# BBB_Breakout_Cape.net
KiCad netlist of a schematic drawn in EAGLE
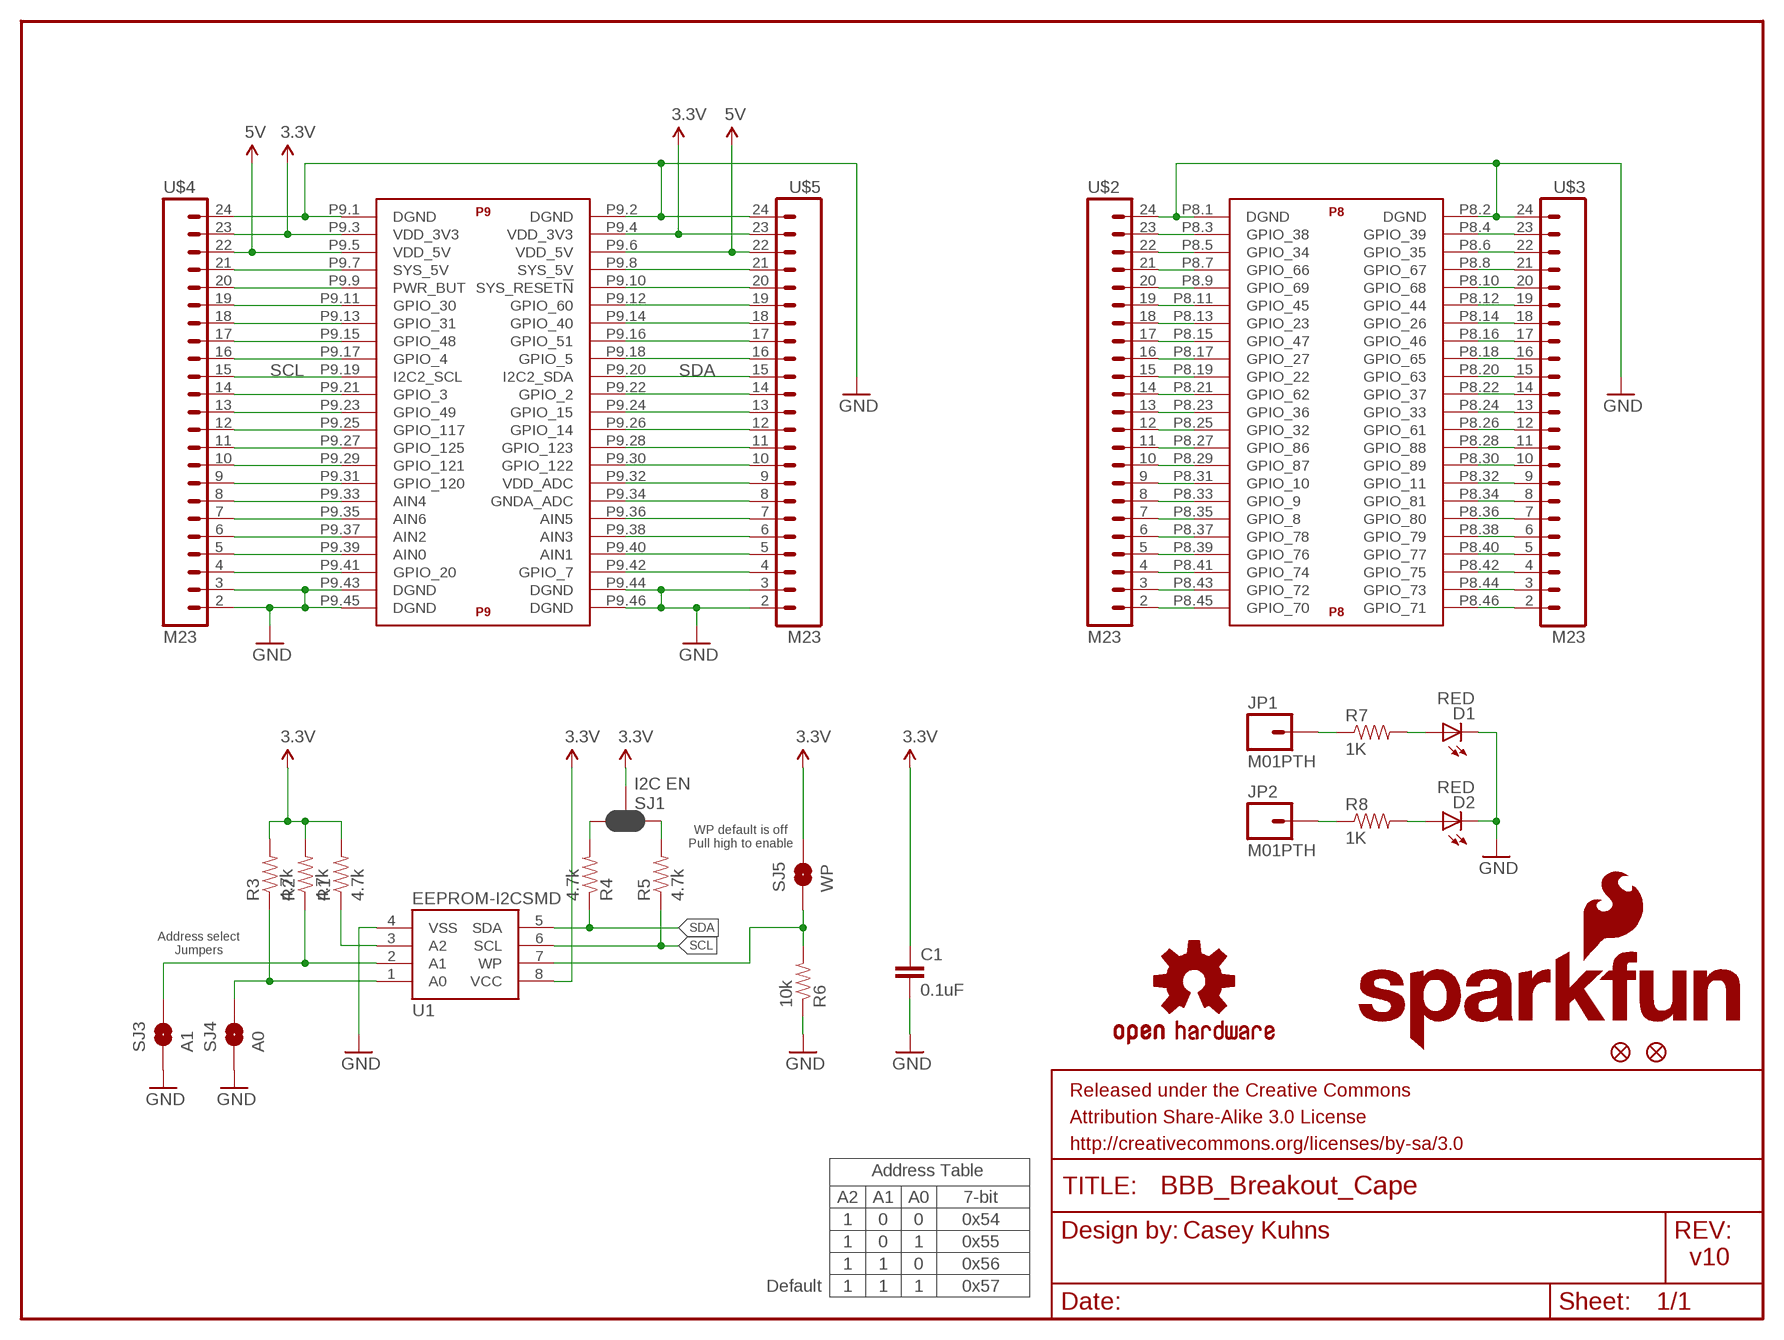
[diagram p0: schematic, sheet 1]

(export (version "E")
  (design (tool "Eeschema 10.0.6"))
  (components
    (comp (ref "C1")
      (value "0.1uF")
      (footprint "eagle-import:0603-CAP")
      (libsource (lib "eagle-import") (part "0.1UF-25V(+80/-20%)(0603)"))
    )
    (comp (ref "D1")
      (value "RED")
      (footprint "eagle-import:LED-0603")
      (libsource (lib "eagle-import") (part "LED-RED0603"))
    )
    (comp (ref "D2")
      (value "RED")
      (footprint "eagle-import:LED-0603")
      (libsource (lib "eagle-import") (part "LED-RED0603"))
    )
    (comp (ref "FID1")
      (value "FIDUCIAL1X2")
      (footprint "eagle-import:FIDUCIAL-1X2")
      (libsource (lib "eagle-import") (part "FIDUCIAL1X2"))
    )
    (comp (ref "FID2")
      (value "FIDUCIAL1X2")
      (footprint "eagle-import:FIDUCIAL-1X2")
      (libsource (lib "eagle-import") (part "FIDUCIAL1X2"))
    )
    (comp (ref "FRAME1")
      (value "FRAME-LETTER")
      (footprint "eagle-import:CREATIVE_COMMONS")
      (libsource (lib "eagle-import") (part "FRAME-LETTER"))
    )
    (comp (ref "JP1")
      (value "M01PTH")
      (footprint "eagle-import:1X01")
      (libsource (lib "eagle-import") (part "M01PTH"))
    )
    (comp (ref "JP2")
      (value "M01PTH")
      (footprint "eagle-import:1X01")
      (libsource (lib "eagle-import") (part "M01PTH"))
    )
    (comp (ref "LOGO2")
      (value "OSHW-LOGOS")
      (footprint "eagle-import:OSHW-LOGO-S")
      (libsource (lib "eagle-import") (part "OSHW-LOGOS"))
    )
    (comp (ref "LOGO3")
      (value "SFE_LOGO_NAME_FLAME.1_INCH")
      (footprint "eagle-import:SFE_LOGO_NAME_FLAME_.1")
      (libsource (lib "eagle-import") (part "SFE_LOGO_NAME_FLAME.1_INCH"))
    )
    (comp (ref "R1")
      (value "4.7k")
      (footprint "eagle-import:0603@1")
      (libsource (lib "eagle-import") (part "4.7KOHM1/10W1%(0603)"))
    )
    (comp (ref "R2")
      (value "4.7k")
      (footprint "eagle-import:0603@1")
      (libsource (lib "eagle-import") (part "4.7KOHM1/10W1%(0603)"))
    )
    (comp (ref "R3")
      (value "4.7k")
      (footprint "eagle-import:0603@1")
      (libsource (lib "eagle-import") (part "4.7KOHM1/10W1%(0603)"))
    )
    (comp (ref "R4")
      (value "4.7k")
      (footprint "eagle-import:0603@1")
      (fields (field (name "PROD_ID") "RES-07857"))
      (libsource (lib "eagle-import") (part "4.7KOHM1/10W1%(0603)"))
    )
    (comp (ref "R5")
      (value "4.7k")
      (footprint "eagle-import:0603@1")
      (fields (field (name "PROD_ID") "RES-07857"))
      (libsource (lib "eagle-import") (part "4.7KOHM1/10W1%(0603)"))
    )
    (comp (ref "R6")
      (value "10k")
      (footprint "eagle-import:0603-RES")
      (libsource (lib "eagle-import") (part "10KOHM1/10W1%(0603)0603"))
    )
    (comp (ref "R7")
      (value "1K")
      (footprint "eagle-import:0603-RES")
      (libsource (lib "eagle-import") (part "1KOHM1/10W1%(0603)"))
    )
    (comp (ref "R8")
      (value "1K")
      (footprint "eagle-import:0603-RES")
      (libsource (lib "eagle-import") (part "1KOHM1/10W1%(0603)"))
    )
    (comp (ref "SJ1")
      (value "I2C EN")
      (footprint "eagle-import:SMT-JUMPER_3_2-NC_PASTE_SILK")
      (libsource (lib "eagle-import") (part "JUMPER-SMT_3_2-NC_PASTE_SILK"))
    )
    (comp (ref "SJ3")
      (value "A1")
      (footprint "eagle-import:SMT-JUMPER_2_NO_SILK")
      (libsource (lib "eagle-import") (part "JUMPER-SMT_2_NO_SILK"))
    )
    (comp (ref "SJ4")
      (value "A0")
      (footprint "eagle-import:SMT-JUMPER_2_NO_SILK")
      (libsource (lib "eagle-import") (part "JUMPER-SMT_2_NO_SILK"))
    )
    (comp (ref "SJ5")
      (value "WP")
      (footprint "eagle-import:SMT-JUMPER_2_NO_SILK")
      (libsource (lib "eagle-import") (part "JUMPER-SMT_2_NO_SILK"))
    )
    (comp (ref "U$1")
      (value "BEAGLE_BONE_BLACK_CAPE")
      (footprint "eagle-import:BEAGLE_BONE_BLACK_CAPE")
      (libsource (lib "eagle-import") (part "BEAGLE_BONE_BLACK_CAPE"))
    )
    (comp (ref "U$2")
      (value "M23")
      (footprint "eagle-import:1X23")
      (libsource (lib "eagle-import") (part "M23"))
    )
    (comp (ref "U$3")
      (value "M23")
      (footprint "eagle-import:1X23")
      (libsource (lib "eagle-import") (part "M23"))
    )
    (comp (ref "U$4")
      (value "M23")
      (footprint "eagle-import:1X23")
      (libsource (lib "eagle-import") (part "M23"))
    )
    (comp (ref "U$5")
      (value "M23")
      (footprint "eagle-import:1X23")
      (libsource (lib "eagle-import") (part "M23"))
    )
    (comp (ref "U1")
      (value "EEPROM-I2CSMD")
      (footprint "eagle-import:SO08")
      (libsource (lib "eagle-import") (part "EEPROM-I2CSMD"))
    )
  )
  (nets
    (net (code "1") (name "3.3V") (class "Default")
      (node (ref "C1") (pin "1") (pinfunction "1_1") (pintype "passive"))
      (node (ref "R1") (pin "2") (pinfunction "2_2") (pintype "passive"))
      (node (ref "R2") (pin "2") (pinfunction "2_2") (pintype "passive"))
      (node (ref "R3") (pin "2") (pinfunction "2_2") (pintype "passive"))
      (node (ref "SJ1") (pin "2") (pinfunction "2_2") (pintype "passive"))
      (node (ref "SJ5") (pin "2") (pinfunction "2_2") (pintype "passive"))
      (node (ref "U$1") (pin "P9.3") (pinfunction "VDD_3V3_P9.3") (pintype "bidirectional"))
      (node (ref "U$1") (pin "P9.4") (pinfunction "VDD_3V3_P9.4") (pintype "bidirectional"))
      (node (ref "U$4") (pin "23") (pinfunction "23_23") (pintype "passive"))
      (node (ref "U$5") (pin "23") (pinfunction "23_23") (pintype "passive"))
      (node (ref "U1") (pin "8") (pinfunction "VCC_8") (pintype "power_in"))
    )
    (net (code "2") (name "5V") (class "Default")
      (node (ref "U$1") (pin "P9.5") (pinfunction "VDD_5V_P9.5") (pintype "bidirectional"))
      (node (ref "U$1") (pin "P9.6") (pinfunction "VDD_5V_P9.6") (pintype "bidirectional"))
      (node (ref "U$4") (pin "22") (pinfunction "22_22") (pintype "passive"))
      (node (ref "U$5") (pin "22") (pinfunction "22_22") (pintype "passive"))
    )
    (net (code "3") (name "GND") (class "Default")
      (node (ref "C1") (pin "2") (pinfunction "2_2") (pintype "passive"))
      (node (ref "D1") (pin "C") (pinfunction "C_C") (pintype "passive"))
      (node (ref "D2") (pin "C") (pinfunction "C_C") (pintype "passive"))
      (node (ref "R6") (pin "1") (pinfunction "1_1") (pintype "passive"))
      (node (ref "SJ3") (pin "1") (pinfunction "1_1") (pintype "passive"))
      (node (ref "SJ4") (pin "1") (pinfunction "1_1") (pintype "passive"))
      (node (ref "U$1") (pin "P8.1") (pinfunction "DGND_P8.1") (pintype "bidirectional"))
      (node (ref "U$1") (pin "P8.2") (pinfunction "DGND_P8.2") (pintype "bidirectional"))
      (node (ref "U$1") (pin "P9.1") (pinfunction "DGND_P9.1") (pintype "bidirectional"))
      (node (ref "U$1") (pin "P9.2") (pinfunction "DGND_P9.2") (pintype "bidirectional"))
      (node (ref "U$1") (pin "P9.43") (pinfunction "DGND_P9.43") (pintype "bidirectional"))
      (node (ref "U$1") (pin "P9.44") (pinfunction "DGND_P9.44") (pintype "bidirectional"))
      (node (ref "U$1") (pin "P9.45") (pinfunction "DGND_P9.45") (pintype "bidirectional"))
      (node (ref "U$1") (pin "P9.46") (pinfunction "DGND_P9.46") (pintype "bidirectional"))
      (node (ref "U$2") (pin "24") (pinfunction "24_24") (pintype "passive"))
      (node (ref "U$3") (pin "24") (pinfunction "24_24") (pintype "passive"))
      (node (ref "U$4") (pin "2") (pinfunction "2_2") (pintype "passive"))
      (node (ref "U$4") (pin "24") (pinfunction "24_24") (pintype "passive"))
      (node (ref "U$4") (pin "3") (pinfunction "3_3") (pintype "passive"))
      (node (ref "U$5") (pin "2") (pinfunction "2_2") (pintype "passive"))
      (node (ref "U$5") (pin "24") (pinfunction "24_24") (pintype "passive"))
      (node (ref "U$5") (pin "3") (pinfunction "3_3") (pintype "passive"))
      (node (ref "U1") (pin "4") (pinfunction "VSS_4") (pintype "power_in"))
    )
    (net (code "4") (name "Net-(D1-PadA)") (class "Default")
      (node (ref "D1") (pin "A") (pinfunction "A_A") (pintype "passive"))
      (node (ref "R7") (pin "2") (pinfunction "2_2") (pintype "passive"))
    )
    (net (code "5") (name "Net-(D2-PadA)") (class "Default")
      (node (ref "D2") (pin "A") (pinfunction "A_A") (pintype "passive"))
      (node (ref "R8") (pin "2") (pinfunction "2_2") (pintype "passive"))
    )
    (net (code "6") (name "Net-(JP1-Pad1)") (class "Default")
      (node (ref "JP1") (pin "1") (pinfunction "1_1") (pintype "passive"))
      (node (ref "R7") (pin "1") (pinfunction "1_1") (pintype "passive"))
    )
    (net (code "7") (name "Net-(JP2-Pad1)") (class "Default")
      (node (ref "JP2") (pin "1") (pinfunction "1_1") (pintype "passive"))
      (node (ref "R8") (pin "1") (pinfunction "1_1") (pintype "passive"))
    )
    (net (code "8") (name "Net-(R4-Pad2)") (class "Default")
      (node (ref "R4") (pin "2") (pinfunction "2_2") (pintype "passive"))
      (node (ref "SJ1") (pin "3") (pinfunction "3_3") (pintype "passive"))
    )
    (net (code "9") (name "Net-(R5-Pad2)") (class "Default")
      (node (ref "R5") (pin "2") (pinfunction "2_2") (pintype "passive"))
      (node (ref "SJ1") (pin "1") (pinfunction "1_1") (pintype "passive"))
    )
    (net (code "10") (name "Net-(U$1A-GPIO_8)") (class "Default")
      (node (ref "U$1") (pin "P8.35") (pinfunction "GPIO_8_P8.35") (pintype "bidirectional"))
      (node (ref "U$2") (pin "7") (pinfunction "7_7") (pintype "passive"))
    )
    (net (code "11") (name "Net-(U$1A-GPIO_9)") (class "Default")
      (node (ref "U$1") (pin "P8.33") (pinfunction "GPIO_9_P8.33") (pintype "bidirectional"))
      (node (ref "U$2") (pin "8") (pinfunction "8_8") (pintype "passive"))
    )
    (net (code "12") (name "Net-(U$1A-GPIO_10)") (class "Default")
      (node (ref "U$1") (pin "P8.31") (pinfunction "GPIO_10_P8.31") (pintype "bidirectional"))
      (node (ref "U$2") (pin "9") (pinfunction "9_9") (pintype "passive"))
    )
    (net (code "13") (name "Net-(U$1A-GPIO_11)") (class "Default")
      (node (ref "U$1") (pin "P8.32") (pinfunction "GPIO_11_P8.32") (pintype "bidirectional"))
      (node (ref "U$3") (pin "9") (pinfunction "9_9") (pintype "passive"))
    )
    (net (code "14") (name "Net-(U$1A-GPIO_22)") (class "Default")
      (node (ref "U$1") (pin "P8.19") (pinfunction "GPIO_22_P8.19") (pintype "bidirectional"))
      (node (ref "U$2") (pin "15") (pinfunction "15_15") (pintype "passive"))
    )
    (net (code "15") (name "Net-(U$1A-GPIO_23)") (class "Default")
      (node (ref "U$1") (pin "P8.13") (pinfunction "GPIO_23_P8.13") (pintype "bidirectional"))
      (node (ref "U$2") (pin "18") (pinfunction "18_18") (pintype "passive"))
    )
    (net (code "16") (name "Net-(U$1A-GPIO_26)") (class "Default")
      (node (ref "U$1") (pin "P8.14") (pinfunction "GPIO_26_P8.14") (pintype "bidirectional"))
      (node (ref "U$3") (pin "18") (pinfunction "18_18") (pintype "passive"))
    )
    (net (code "17") (name "Net-(U$1A-GPIO_27)") (class "Default")
      (node (ref "U$1") (pin "P8.17") (pinfunction "GPIO_27_P8.17") (pintype "bidirectional"))
      (node (ref "U$2") (pin "16") (pinfunction "16_16") (pintype "passive"))
    )
    (net (code "18") (name "Net-(U$1A-GPIO_32)") (class "Default")
      (node (ref "U$1") (pin "P8.25") (pinfunction "GPIO_32_P8.25") (pintype "bidirectional"))
      (node (ref "U$2") (pin "12") (pinfunction "12_12") (pintype "passive"))
    )
    (net (code "19") (name "Net-(U$1A-GPIO_33)") (class "Default")
      (node (ref "U$1") (pin "P8.24") (pinfunction "GPIO_33_P8.24") (pintype "bidirectional"))
      (node (ref "U$3") (pin "13") (pinfunction "13_13") (pintype "passive"))
    )
    (net (code "20") (name "Net-(U$1A-GPIO_34)") (class "Default")
      (node (ref "U$1") (pin "P8.5") (pinfunction "GPIO_34_P8.5") (pintype "bidirectional"))
      (node (ref "U$2") (pin "22") (pinfunction "22_22") (pintype "passive"))
    )
    (net (code "21") (name "Net-(U$1A-GPIO_35)") (class "Default")
      (node (ref "U$1") (pin "P8.6") (pinfunction "GPIO_35_P8.6") (pintype "bidirectional"))
      (node (ref "U$3") (pin "22") (pinfunction "22_22") (pintype "passive"))
    )
    (net (code "22") (name "Net-(U$1A-GPIO_36)") (class "Default")
      (node (ref "U$1") (pin "P8.23") (pinfunction "GPIO_36_P8.23") (pintype "bidirectional"))
      (node (ref "U$2") (pin "13") (pinfunction "13_13") (pintype "passive"))
    )
    (net (code "23") (name "Net-(U$1A-GPIO_37)") (class "Default")
      (node (ref "U$1") (pin "P8.22") (pinfunction "GPIO_37_P8.22") (pintype "bidirectional"))
      (node (ref "U$3") (pin "14") (pinfunction "14_14") (pintype "passive"))
    )
    (net (code "24") (name "Net-(U$1A-GPIO_38)") (class "Default")
      (node (ref "U$1") (pin "P8.3") (pinfunction "GPIO_38_P8.3") (pintype "bidirectional"))
      (node (ref "U$2") (pin "23") (pinfunction "23_23") (pintype "passive"))
    )
    (net (code "25") (name "Net-(U$1A-GPIO_39)") (class "Default")
      (node (ref "U$1") (pin "P8.4") (pinfunction "GPIO_39_P8.4") (pintype "bidirectional"))
      (node (ref "U$3") (pin "23") (pinfunction "23_23") (pintype "passive"))
    )
    (net (code "26") (name "Net-(U$1A-GPIO_44)") (class "Default")
      (node (ref "U$1") (pin "P8.12") (pinfunction "GPIO_44_P8.12") (pintype "bidirectional"))
      (node (ref "U$3") (pin "19") (pinfunction "19_19") (pintype "passive"))
    )
    (net (code "27") (name "Net-(U$1A-GPIO_45)") (class "Default")
      (node (ref "U$1") (pin "P8.11") (pinfunction "GPIO_45_P8.11") (pintype "bidirectional"))
      (node (ref "U$2") (pin "19") (pinfunction "19_19") (pintype "passive"))
    )
    (net (code "28") (name "Net-(U$1A-GPIO_46)") (class "Default")
      (node (ref "U$1") (pin "P8.16") (pinfunction "GPIO_46_P8.16") (pintype "bidirectional"))
      (node (ref "U$3") (pin "17") (pinfunction "17_17") (pintype "passive"))
    )
    (net (code "29") (name "Net-(U$1A-GPIO_47)") (class "Default")
      (node (ref "U$1") (pin "P8.15") (pinfunction "GPIO_47_P8.15") (pintype "bidirectional"))
      (node (ref "U$2") (pin "17") (pinfunction "17_17") (pintype "passive"))
    )
    (net (code "30") (name "Net-(U$1A-GPIO_61)") (class "Default")
      (node (ref "U$1") (pin "P8.26") (pinfunction "GPIO_61_P8.26") (pintype "bidirectional"))
      (node (ref "U$3") (pin "12") (pinfunction "12_12") (pintype "passive"))
    )
    (net (code "31") (name "Net-(U$1A-GPIO_62)") (class "Default")
      (node (ref "U$1") (pin "P8.21") (pinfunction "GPIO_62_P8.21") (pintype "bidirectional"))
      (node (ref "U$2") (pin "14") (pinfunction "14_14") (pintype "passive"))
    )
    (net (code "32") (name "Net-(U$1A-GPIO_63)") (class "Default")
      (node (ref "U$1") (pin "P8.20") (pinfunction "GPIO_63_P8.20") (pintype "bidirectional"))
      (node (ref "U$3") (pin "15") (pinfunction "15_15") (pintype "passive"))
    )
    (net (code "33") (name "Net-(U$1A-GPIO_65)") (class "Default")
      (node (ref "U$1") (pin "P8.18") (pinfunction "GPIO_65_P8.18") (pintype "bidirectional"))
      (node (ref "U$3") (pin "16") (pinfunction "16_16") (pintype "passive"))
    )
    (net (code "34") (name "Net-(U$1A-GPIO_66)") (class "Default")
      (node (ref "U$1") (pin "P8.7") (pinfunction "GPIO_66_P8.7") (pintype "bidirectional"))
      (node (ref "U$2") (pin "21") (pinfunction "21_21") (pintype "passive"))
    )
    (net (code "35") (name "Net-(U$1A-GPIO_67)") (class "Default")
      (node (ref "U$1") (pin "P8.8") (pinfunction "GPIO_67_P8.8") (pintype "bidirectional"))
      (node (ref "U$3") (pin "21") (pinfunction "21_21") (pintype "passive"))
    )
    (net (code "36") (name "Net-(U$1A-GPIO_68)") (class "Default")
      (node (ref "U$1") (pin "P8.10") (pinfunction "GPIO_68_P8.10") (pintype "bidirectional"))
      (node (ref "U$3") (pin "20") (pinfunction "20_20") (pintype "passive"))
    )
    (net (code "37") (name "Net-(U$1A-GPIO_69)") (class "Default")
      (node (ref "U$1") (pin "P8.9") (pinfunction "GPIO_69_P8.9") (pintype "bidirectional"))
      (node (ref "U$2") (pin "20") (pinfunction "20_20") (pintype "passive"))
    )
    (net (code "38") (name "Net-(U$1A-GPIO_70)") (class "Default")
      (node (ref "U$1") (pin "P8.45") (pinfunction "GPIO_70_P8.45") (pintype "bidirectional"))
      (node (ref "U$2") (pin "2") (pinfunction "2_2") (pintype "passive"))
    )
    (net (code "39") (name "Net-(U$1A-GPIO_71)") (class "Default")
      (node (ref "U$1") (pin "P8.46") (pinfunction "GPIO_71_P8.46") (pintype "bidirectional"))
      (node (ref "U$3") (pin "2") (pinfunction "2_2") (pintype "passive"))
    )
    (net (code "40") (name "Net-(U$1A-GPIO_72)") (class "Default")
      (node (ref "U$1") (pin "P8.43") (pinfunction "GPIO_72_P8.43") (pintype "bidirectional"))
      (node (ref "U$2") (pin "3") (pinfunction "3_3") (pintype "passive"))
    )
    (net (code "41") (name "Net-(U$1A-GPIO_73)") (class "Default")
      (node (ref "U$1") (pin "P8.44") (pinfunction "GPIO_73_P8.44") (pintype "bidirectional"))
      (node (ref "U$3") (pin "3") (pinfunction "3_3") (pintype "passive"))
    )
    (net (code "42") (name "Net-(U$1A-GPIO_74)") (class "Default")
      (node (ref "U$1") (pin "P8.41") (pinfunction "GPIO_74_P8.41") (pintype "bidirectional"))
      (node (ref "U$2") (pin "4") (pinfunction "4_4") (pintype "passive"))
    )
    (net (code "43") (name "Net-(U$1A-GPIO_75)") (class "Default")
      (node (ref "U$1") (pin "P8.42") (pinfunction "GPIO_75_P8.42") (pintype "bidirectional"))
      (node (ref "U$3") (pin "4") (pinfunction "4_4") (pintype "passive"))
    )
    (net (code "44") (name "Net-(U$1A-GPIO_76)") (class "Default")
      (node (ref "U$1") (pin "P8.39") (pinfunction "GPIO_76_P8.39") (pintype "bidirectional"))
      (node (ref "U$2") (pin "5") (pinfunction "5_5") (pintype "passive"))
    )
    (net (code "45") (name "Net-(U$1A-GPIO_77)") (class "Default")
      (node (ref "U$1") (pin "P8.40") (pinfunction "GPIO_77_P8.40") (pintype "bidirectional"))
      (node (ref "U$3") (pin "5") (pinfunction "5_5") (pintype "passive"))
    )
    (net (code "46") (name "Net-(U$1A-GPIO_78)") (class "Default")
      (node (ref "U$1") (pin "P8.37") (pinfunction "GPIO_78_P8.37") (pintype "bidirectional"))
      (node (ref "U$2") (pin "6") (pinfunction "6_6") (pintype "passive"))
    )
    (net (code "47") (name "Net-(U$1A-GPIO_79)") (class "Default")
      (node (ref "U$1") (pin "P8.38") (pinfunction "GPIO_79_P8.38") (pintype "bidirectional"))
      (node (ref "U$3") (pin "6") (pinfunction "6_6") (pintype "passive"))
    )
    (net (code "48") (name "Net-(U$1A-GPIO_80)") (class "Default")
      (node (ref "U$1") (pin "P8.36") (pinfunction "GPIO_80_P8.36") (pintype "bidirectional"))
      (node (ref "U$3") (pin "7") (pinfunction "7_7") (pintype "passive"))
    )
    (net (code "49") (name "Net-(U$1A-GPIO_81)") (class "Default")
      (node (ref "U$1") (pin "P8.34") (pinfunction "GPIO_81_P8.34") (pintype "bidirectional"))
      (node (ref "U$3") (pin "8") (pinfunction "8_8") (pintype "passive"))
    )
    (net (code "50") (name "Net-(U$1A-GPIO_86)") (class "Default")
      (node (ref "U$1") (pin "P8.27") (pinfunction "GPIO_86_P8.27") (pintype "bidirectional"))
      (node (ref "U$2") (pin "11") (pinfunction "11_11") (pintype "passive"))
    )
    (net (code "51") (name "Net-(U$1A-GPIO_87)") (class "Default")
      (node (ref "U$1") (pin "P8.29") (pinfunction "GPIO_87_P8.29") (pintype "bidirectional"))
      (node (ref "U$2") (pin "10") (pinfunction "10_10") (pintype "passive"))
    )
    (net (code "52") (name "Net-(U$1A-GPIO_88)") (class "Default")
      (node (ref "U$1") (pin "P8.28") (pinfunction "GPIO_88_P8.28") (pintype "bidirectional"))
      (node (ref "U$3") (pin "11") (pinfunction "11_11") (pintype "passive"))
    )
    (net (code "53") (name "Net-(U$1A-GPIO_89)") (class "Default")
      (node (ref "U$1") (pin "P8.30") (pinfunction "GPIO_89_P8.30") (pintype "bidirectional"))
      (node (ref "U$3") (pin "10") (pinfunction "10_10") (pintype "passive"))
    )
    (net (code "54") (name "Net-(U$1B-AIN0)") (class "Default")
      (node (ref "U$1") (pin "P9.39") (pinfunction "AIN0_P9.39") (pintype "bidirectional"))
      (node (ref "U$4") (pin "5") (pinfunction "5_5") (pintype "passive"))
    )
    (net (code "55") (name "Net-(U$1B-AIN1)") (class "Default")
      (node (ref "U$1") (pin "P9.40") (pinfunction "AIN1_P9.40") (pintype "bidirectional"))
      (node (ref "U$5") (pin "5") (pinfunction "5_5") (pintype "passive"))
    )
    (net (code "56") (name "Net-(U$1B-AIN2)") (class "Default")
      (node (ref "U$1") (pin "P9.37") (pinfunction "AIN2_P9.37") (pintype "bidirectional"))
      (node (ref "U$4") (pin "6") (pinfunction "6_6") (pintype "passive"))
    )
    (net (code "57") (name "Net-(U$1B-AIN3)") (class "Default")
      (node (ref "U$1") (pin "P9.38") (pinfunction "AIN3_P9.38") (pintype "bidirectional"))
      (node (ref "U$5") (pin "6") (pinfunction "6_6") (pintype "passive"))
    )
    (net (code "58") (name "Net-(U$1B-AIN4)") (class "Default")
      (node (ref "U$1") (pin "P9.33") (pinfunction "AIN4_P9.33") (pintype "bidirectional"))
      (node (ref "U$4") (pin "8") (pinfunction "8_8") (pintype "passive"))
    )
    (net (code "59") (name "Net-(U$1B-AIN5)") (class "Default")
      (node (ref "U$1") (pin "P9.36") (pinfunction "AIN5_P9.36") (pintype "bidirectional"))
      (node (ref "U$5") (pin "7") (pinfunction "7_7") (pintype "passive"))
    )
    (net (code "60") (name "Net-(U$1B-AIN6)") (class "Default")
      (node (ref "U$1") (pin "P9.35") (pinfunction "AIN6_P9.35") (pintype "bidirectional"))
      (node (ref "U$4") (pin "7") (pinfunction "7_7") (pintype "passive"))
    )
    (net (code "61") (name "Net-(U$1B-GNDA_ADC)") (class "Default")
      (node (ref "U$1") (pin "P9.34") (pinfunction "GNDA_ADC_P9.34") (pintype "bidirectional"))
      (node (ref "U$5") (pin "8") (pinfunction "8_8") (pintype "passive"))
    )
    (net (code "62") (name "Net-(U$1B-GPIO_2)") (class "Default")
      (node (ref "U$1") (pin "P9.22") (pinfunction "GPIO_2_P9.22") (pintype "bidirectional"))
      (node (ref "U$5") (pin "14") (pinfunction "14_14") (pintype "passive"))
    )
    (net (code "63") (name "Net-(U$1B-GPIO_3)") (class "Default")
      (node (ref "U$1") (pin "P9.21") (pinfunction "GPIO_3_P9.21") (pintype "bidirectional"))
      (node (ref "U$4") (pin "14") (pinfunction "14_14") (pintype "passive"))
    )
    (net (code "64") (name "Net-(U$1B-GPIO_4)") (class "Default")
      (node (ref "U$1") (pin "P9.17") (pinfunction "GPIO_4_P9.17") (pintype "bidirectional"))
      (node (ref "U$4") (pin "16") (pinfunction "16_16") (pintype "passive"))
    )
    (net (code "65") (name "Net-(U$1B-GPIO_5)") (class "Default")
      (node (ref "U$1") (pin "P9.18") (pinfunction "GPIO_5_P9.18") (pintype "bidirectional"))
      (node (ref "U$5") (pin "16") (pinfunction "16_16") (pintype "passive"))
    )
    (net (code "66") (name "Net-(U$1B-GPIO_7)") (class "Default")
      (node (ref "U$1") (pin "P9.42") (pinfunction "GPIO_7_P9.42") (pintype "bidirectional"))
      (node (ref "U$5") (pin "4") (pinfunction "4_4") (pintype "passive"))
    )
    (net (code "67") (name "Net-(U$1B-GPIO_14)") (class "Default")
      (node (ref "U$1") (pin "P9.26") (pinfunction "GPIO_14_P9.26") (pintype "bidirectional"))
      (node (ref "U$5") (pin "12") (pinfunction "12_12") (pintype "passive"))
    )
    (net (code "68") (name "Net-(U$1B-GPIO_15)") (class "Default")
      (node (ref "U$1") (pin "P9.24") (pinfunction "GPIO_15_P9.24") (pintype "bidirectional"))
      (node (ref "U$5") (pin "13") (pinfunction "13_13") (pintype "passive"))
    )
    (net (code "69") (name "Net-(U$1B-GPIO_20)") (class "Default")
      (node (ref "U$1") (pin "P9.41") (pinfunction "GPIO_20_P9.41") (pintype "bidirectional"))
      (node (ref "U$4") (pin "4") (pinfunction "4_4") (pintype "passive"))
    )
    (net (code "70") (name "Net-(U$1B-GPIO_30)") (class "Default")
      (node (ref "U$1") (pin "P9.11") (pinfunction "GPIO_30_P9.11") (pintype "bidirectional"))
      (node (ref "U$4") (pin "19") (pinfunction "19_19") (pintype "passive"))
    )
    (net (code "71") (name "Net-(U$1B-GPIO_31)") (class "Default")
      (node (ref "U$1") (pin "P9.13") (pinfunction "GPIO_31_P9.13") (pintype "bidirectional"))
      (node (ref "U$4") (pin "18") (pinfunction "18_18") (pintype "passive"))
    )
    (net (code "72") (name "Net-(U$1B-GPIO_40)") (class "Default")
      (node (ref "U$1") (pin "P9.14") (pinfunction "GPIO_40_P9.14") (pintype "bidirectional"))
      (node (ref "U$5") (pin "18") (pinfunction "18_18") (pintype "passive"))
    )
    (net (code "73") (name "Net-(U$1B-GPIO_48)") (class "Default")
      (node (ref "U$1") (pin "P9.15") (pinfunction "GPIO_48_P9.15") (pintype "bidirectional"))
      (node (ref "U$4") (pin "17") (pinfunction "17_17") (pintype "passive"))
    )
    (net (code "74") (name "Net-(U$1B-GPIO_49)") (class "Default")
      (node (ref "U$1") (pin "P9.23") (pinfunction "GPIO_49_P9.23") (pintype "bidirectional"))
      (node (ref "U$4") (pin "13") (pinfunction "13_13") (pintype "passive"))
    )
    (net (code "75") (name "Net-(U$1B-GPIO_51)") (class "Default")
      (node (ref "U$1") (pin "P9.16") (pinfunction "GPIO_51_P9.16") (pintype "bidirectional"))
      (node (ref "U$5") (pin "17") (pinfunction "17_17") (pintype "passive"))
    )
    (net (code "76") (name "Net-(U$1B-GPIO_60)") (class "Default")
      (node (ref "U$1") (pin "P9.12") (pinfunction "GPIO_60_P9.12") (pintype "bidirectional"))
      (node (ref "U$5") (pin "19") (pinfunction "19_19") (pintype "passive"))
    )
    (net (code "77") (name "Net-(U$1B-GPIO_117)") (class "Default")
      (node (ref "U$1") (pin "P9.25") (pinfunction "GPIO_117_P9.25") (pintype "bidirectional"))
      (node (ref "U$4") (pin "12") (pinfunction "12_12") (pintype "passive"))
    )
    (net (code "78") (name "Net-(U$1B-GPIO_120)") (class "Default")
      (node (ref "U$1") (pin "P9.31") (pinfunction "GPIO_120_P9.31") (pintype "bidirectional"))
      (node (ref "U$4") (pin "9") (pinfunction "9_9") (pintype "passive"))
    )
    (net (code "79") (name "Net-(U$1B-GPIO_121)") (class "Default")
      (node (ref "U$1") (pin "P9.29") (pinfunction "GPIO_121_P9.29") (pintype "bidirectional"))
      (node (ref "U$4") (pin "10") (pinfunction "10_10") (pintype "passive"))
    )
    (net (code "80") (name "Net-(U$1B-GPIO_122)") (class "Default")
      (node (ref "U$1") (pin "P9.30") (pinfunction "GPIO_122_P9.30") (pintype "bidirectional"))
      (node (ref "U$5") (pin "10") (pinfunction "10_10") (pintype "passive"))
    )
    (net (code "81") (name "Net-(U$1B-GPIO_123)") (class "Default")
      (node (ref "U$1") (pin "P9.28") (pinfunction "GPIO_123_P9.28") (pintype "bidirectional"))
      (node (ref "U$5") (pin "11") (pinfunction "11_11") (pintype "passive"))
    )
    (net (code "82") (name "Net-(U$1B-GPIO_125)") (class "Default")
      (node (ref "U$1") (pin "P9.27") (pinfunction "GPIO_125_P9.27") (pintype "bidirectional"))
      (node (ref "U$4") (pin "11") (pinfunction "11_11") (pintype "passive"))
    )
    (net (code "83") (name "Net-(U$1B-PWR_BUT)") (class "Default")
      (node (ref "U$1") (pin "P9.9") (pinfunction "PWR_BUT_P9.9") (pintype "bidirectional"))
      (node (ref "U$4") (pin "20") (pinfunction "20_20") (pintype "passive"))
    )
    (net (code "84") (name "Net-(U$1B-SYS_5V-PadP9.7)") (class "Default")
      (node (ref "U$1") (pin "P9.7") (pinfunction "SYS_5V_P9.7") (pintype "bidirectional"))
      (node (ref "U$4") (pin "21") (pinfunction "21_21") (pintype "passive"))
    )
    (net (code "85") (name "Net-(U$1B-SYS_5V-PadP9.8)") (class "Default")
      (node (ref "U$1") (pin "P9.8") (pinfunction "SYS_5V_P9.8") (pintype "bidirectional"))
      (node (ref "U$5") (pin "21") (pinfunction "21_21") (pintype "passive"))
    )
    (net (code "86") (name "Net-(U$1B-SYS_RESET~{N})") (class "Default")
      (node (ref "U$1") (pin "P9.10") (pinfunction "SYS_RESET~{N}_P9.10") (pintype "bidirectional"))
      (node (ref "U$5") (pin "20") (pinfunction "20_20") (pintype "passive"))
    )
    (net (code "87") (name "Net-(U$1B-VDD_ADC)") (class "Default")
      (node (ref "U$1") (pin "P9.32") (pinfunction "VDD_ADC_P9.32") (pintype "bidirectional"))
      (node (ref "U$5") (pin "9") (pinfunction "9_9") (pintype "passive"))
    )
    (net (code "88") (name "Net-(U1-A0)") (class "Default")
      (node (ref "R3") (pin "1") (pinfunction "1_1") (pintype "passive"))
      (node (ref "SJ4") (pin "2") (pinfunction "2_2") (pintype "passive"))
      (node (ref "U1") (pin "1") (pinfunction "A0_1") (pintype "bidirectional"))
    )
    (net (code "89") (name "Net-(U1-A1)") (class "Default")
      (node (ref "R2") (pin "1") (pinfunction "1_1") (pintype "passive"))
      (node (ref "SJ3") (pin "2") (pinfunction "2_2") (pintype "passive"))
      (node (ref "U1") (pin "2") (pinfunction "A1_2") (pintype "bidirectional"))
    )
    (net (code "90") (name "Net-(U1-A2)") (class "Default")
      (node (ref "R1") (pin "1") (pinfunction "1_1") (pintype "passive"))
      (node (ref "U1") (pin "3") (pinfunction "A2_3") (pintype "bidirectional"))
    )
    (net (code "91") (name "Net-(U1-WP)") (class "Default")
      (node (ref "R6") (pin "2") (pinfunction "2_2") (pintype "passive"))
      (node (ref "SJ5") (pin "1") (pinfunction "1_1") (pintype "passive"))
      (node (ref "U1") (pin "7") (pinfunction "WP_7") (pintype "bidirectional"))
    )
    (net (code "92") (name "SCL") (class "Default")
      (node (ref "R5") (pin "1") (pinfunction "1_1") (pintype "passive"))
      (node (ref "U$1") (pin "P9.19") (pinfunction "I2C2_SCL_P9.19") (pintype "bidirectional"))
      (node (ref "U$4") (pin "15") (pinfunction "15_15") (pintype "passive"))
      (node (ref "U1") (pin "6") (pinfunction "SCL_6") (pintype "bidirectional"))
    )
    (net (code "93") (name "SDA") (class "Default")
      (node (ref "R4") (pin "1") (pinfunction "1_1") (pintype "passive"))
      (node (ref "U$1") (pin "P9.20") (pinfunction "I2C2_SDA_P9.20") (pintype "bidirectional"))
      (node (ref "U$5") (pin "15") (pinfunction "15_15") (pintype "passive"))
      (node (ref "U1") (pin "5") (pinfunction "SDA_5") (pintype "bidirectional"))
    )
  )
)
